# MCU.net
KiCad netlist of a schematic drawn in Altium Designer
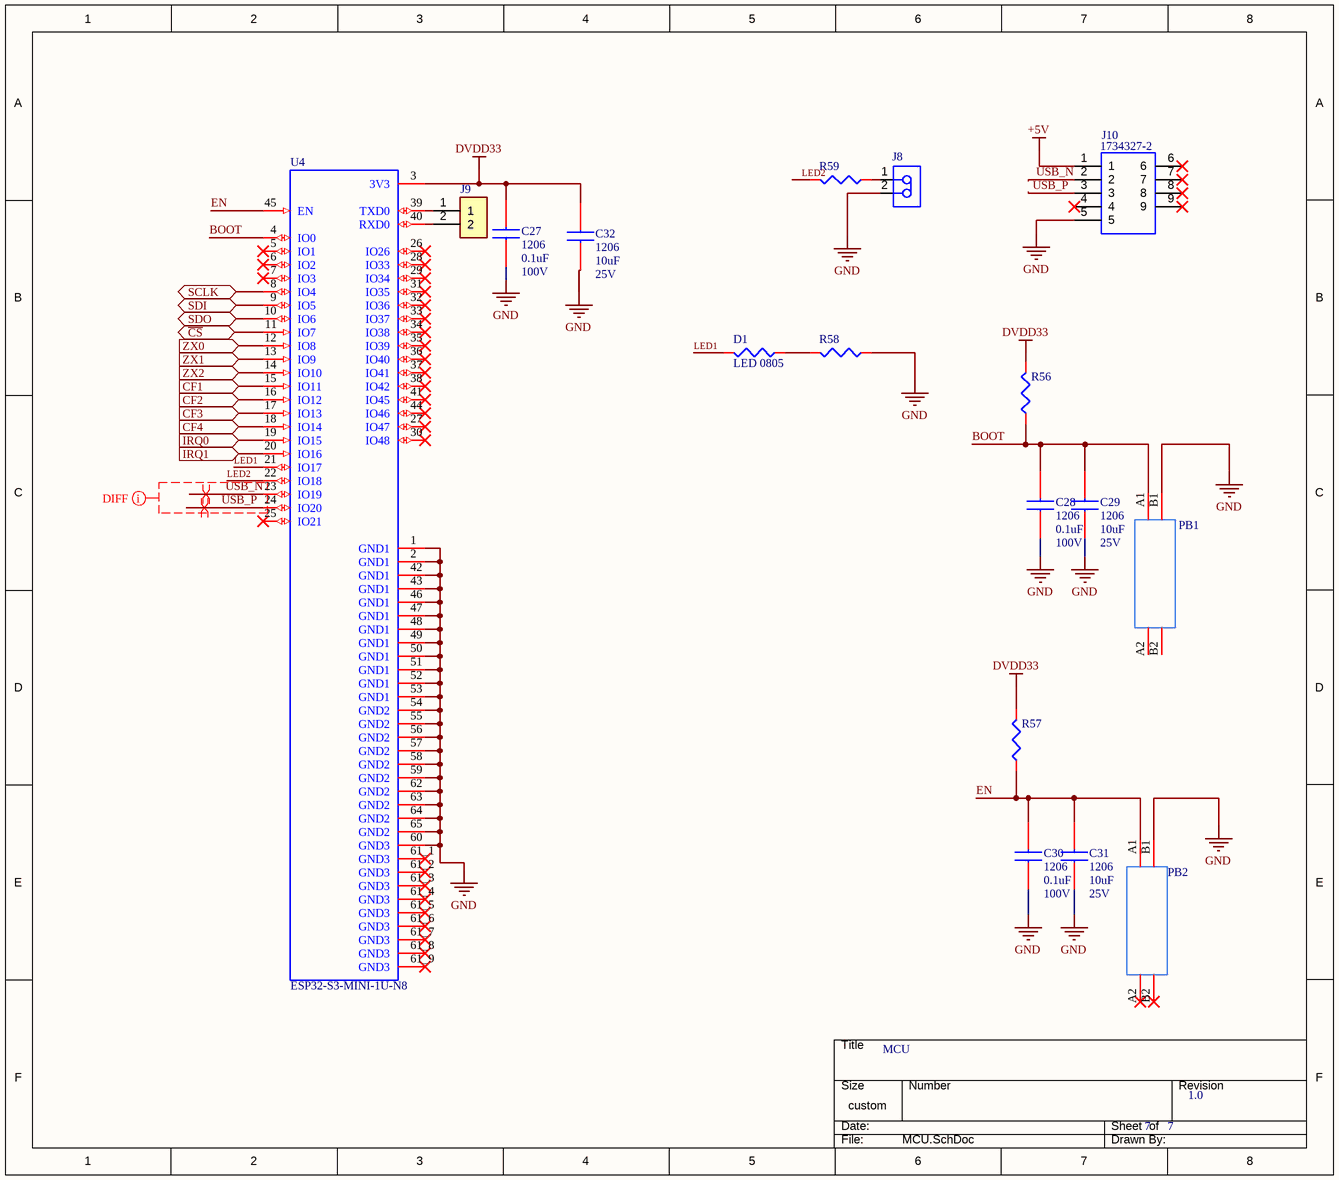
[diagram p0: MCU.SchDoc]

(export (version "E")
  (design (tool "Eeschema 10.0.6"))
  (components
    (comp (ref "C27")
      (value "C1206C104J1RACAUTO")
      (footprint "CAPC3316X180N")
      (description "Multilayer Ceramic Capacitors MLCC - SMD/SMT 100V 0.1uF X7R 1206 5% AEC-Q200")
      (fields
        (field (name "MOUSER PART NUMBER") "80-C1206X224KARAUTO")
        (field (name "MANUFACTURER_PART_NUMBER") "C1206X224KARACAUTO")
        (field (name "SIZE") "1206")
        (field (name "CAPACITANCE") "0.1uF")
        (field (name "VOLTAGE") "100V")
      )
      (libsource (lib "C1206X224KARACAUTO") (part "C1206X224KARACAUTO"))
    )
    (comp (ref "C28")
      (value "C1206C104J1RACAUTO")
      (footprint "CAPC3316X180N")
      (description "Multilayer Ceramic Capacitors MLCC - SMD/SMT 100V 0.1uF X7R 1206 5% AEC-Q200")
      (fields
        (field (name "MOUSER PART NUMBER") "80-C1206X224KARAUTO")
        (field (name "MANUFACTURER_PART_NUMBER") "C1206X224KARACAUTO")
        (field (name "SIZE") "1206")
        (field (name "CAPACITANCE") "0.1uF")
        (field (name "VOLTAGE") "100V")
      )
      (libsource (lib "C1206X224KARACAUTO") (part "C1206X224KARACAUTO"))
    )
    (comp (ref "C29")
      (value "MBAST31LAB7106KTNA01")
      (footprint "CAPC3316X180N")
      (description "Multilayer Ceramic Capacitors MLCC - SMD/SMT 25V 10uF X7R 1206 10%")
      (fields
        (field (name "MOUSER PART NUMBER") "80-C1206X224KARAUTO")
        (field (name "MANUFACTURER_PART_NUMBER") "C1206X224KARACAUTO")
        (field (name "SIZE") "1206")
        (field (name "CAPACITANCE") "10uF")
        (field (name "VOLTAGE") "25V")
      )
      (libsource (lib "C1206X224KARACAUTO") (part "C1206X224KARACAUTO"))
    )
    (comp (ref "C30")
      (value "C1206C104J1RACAUTO")
      (footprint "CAPC3316X180N")
      (description "Multilayer Ceramic Capacitors MLCC - SMD/SMT 100V 0.1uF X7R 1206 5% AEC-Q200")
      (fields
        (field (name "MOUSER PART NUMBER") "80-C1206X224KARAUTO")
        (field (name "MANUFACTURER_PART_NUMBER") "C1206X224KARACAUTO")
        (field (name "SIZE") "1206")
        (field (name "CAPACITANCE") "0.1uF")
        (field (name "VOLTAGE") "100V")
      )
      (libsource (lib "C1206X224KARACAUTO") (part "C1206X224KARACAUTO"))
    )
    (comp (ref "C31")
      (value "MBAST31LAB7106KTNA01")
      (footprint "CAPC3316X180N")
      (description "Multilayer Ceramic Capacitors MLCC - SMD/SMT 25V 10uF X7R 1206 10%")
      (fields
        (field (name "MOUSER PART NUMBER") "80-C1206X224KARAUTO")
        (field (name "MANUFACTURER_PART_NUMBER") "C1206X224KARACAUTO")
        (field (name "SIZE") "1206")
        (field (name "CAPACITANCE") "10uF")
        (field (name "VOLTAGE") "25V")
      )
      (libsource (lib "C1206X224KARACAUTO") (part "C1206X224KARACAUTO"))
    )
    (comp (ref "C32")
      (value "MBAST31LAB7106KTNA01")
      (footprint "CAPC3316X180N")
      (description "Multilayer Ceramic Capacitors MLCC - SMD/SMT 25V 10uF X7R 1206 10%")
      (fields
        (field (name "MOUSER PART NUMBER") "80-C1206X224KARAUTO")
        (field (name "MANUFACTURER_PART_NUMBER") "C1206X224KARACAUTO")
        (field (name "SIZE") "1206")
        (field (name "CAPACITANCE") "10uF")
        (field (name "VOLTAGE") "25V")
      )
      (libsource (lib "C1206X224KARACAUTO") (part "C1206X224KARACAUTO"))
    )
    (comp (ref "D1")
      (value "LED 0805")
      (footprint "RESC2013X84N")
      (description "Thin Film Resistors - SMD 0805 1000ohms 25ppm 0.5% AEC-Q200")
      (fields
        (field (name "MANUFACTURER_PART_NUMBER") "ERA-6AED102V")
        (field (name "MOUSER PART NUMBER") "667-ERA-6AED102V")
      )
      (libsource (lib "ERA-6AED102V") (part "ERA-6AED102V"))
    )
    (comp (ref "J8")
      (value "B2B-PH-K-S(LF)(SN)")
      (footprint "JST-B2B-PH-K-S_V")
      (fields (field (name "MANUFACTURER") "JST"))
      (libsource (lib "Altium Content Vault") (part "CN-2P-F-QF2"))
    )
    (comp (ref "J9")
      (value "HTSW-102-07-G-S")
      (footprint "HDRV2W64P0X254_1X2_508X248X838P")
      (description "Samtec, HTSW, 2 Way, 1 Row, Vertical Pin Header")
      (fields (field (name "MOUSER PART NUMBER") "200-HTSW10207GS"))
      (libsource (lib "HTSW-102-07-G-S") (part "HTSW-102-07-G-S"))
    )
    (comp (ref "J10")
      (value "1734327-2")
      (footprint "17343272")
      (description "Body Features: Offset 0 MM")
      (fields (field (name "MOUSER PART NUMBER") "571-1734327-2"))
      (libsource (lib "1734327-2") (part "1734327-2"))
    )
    (comp (ref "PB1")
      (value "EVP-BV2C3L000")
      (footprint "EVPBV2C3L000")
      (description "Tactile Switches 6.5mm 6.2mm SMD Op Force 1.6N")
      (fields (field (name "MOUSER PART NUMBER") "667-EVP-BV2C3L000"))
      (libsource (lib "EVP-BV2C3L000") (part "EVP-BV2C3L000"))
    )
    (comp (ref "PB2")
      (value "EVP-BV2C3L000")
      (footprint "EVPBV2C3L000")
      (description "Tactile Switches 6.5mm 6.2mm SMD Op Force 1.6N")
      (fields (field (name "MOUSER PART NUMBER") "667-EVP-BV2C3L000"))
      (libsource (lib "EVP-BV2C3L000") (part "EVP-BV2C3L000"))
    )
    (comp (ref "R56")
      (value "ERA-6AED102V")
      (footprint "RESC2013X84N")
      (description "Thin Film Resistors - SMD 0805 1000ohms 25ppm 0.5% AEC-Q200")
      (fields (field (name "MOUSER PART NUMBER") "667-ERA-6AED102V"))
      (libsource (lib "ERA-6AED102V") (part "ERA-6AED102V"))
    )
    (comp (ref "R57")
      (value "ERA-6AED102V")
      (footprint "RESC2013X84N")
      (description "Thin Film Resistors - SMD 0805 1000ohms 25ppm 0.5% AEC-Q200")
      (fields (field (name "MOUSER PART NUMBER") "667-ERA-6AED102V"))
      (libsource (lib "ERA-6AED102V") (part "ERA-6AED102V"))
    )
    (comp (ref "R58")
      (value "ERA-6AED102V")
      (footprint "RESC2013X84N")
      (description "Thin Film Resistors - SMD 0805 330ohms 25ppm 0.5% AEC-Q200")
      (fields (field (name "MOUSER PART NUMBER") "667-ERA-6AED102V"))
      (libsource (lib "ERA-6AED102V") (part "ERA-6AED102V"))
    )
    (comp (ref "R59")
      (value "ERA-6AED102V")
      (footprint "RESC2013X84N")
      (description "0805 330R")
      (fields (field (name "MOUSER PART NUMBER") "667-ERA-6AED102V"))
      (libsource (lib "ERA-6AED102V") (part "ERA-6AED102V"))
    )
    (comp (ref "U4")
      (value "ESP32-S3-MINI-1U-N8")
      (footprint "XCVR_ESP32-S3-MINI-1U-N8")
      (fields (field (name "MF") "Espressif Systems"))
      (libsource (lib "ESP32-S3-MINI-1U-N8") (part "ESP32-S3-MINI-1U-N8"))
    )
  )
  (nets
    (net (code "1") (name "+5V") (class "Default")
      (node (ref "J10") (pin "1") (pinfunction "1_1") (pintype "passive"))
    )
    (net (code "2") (name "/BOOT") (class "Default")
      (node (ref "C28") (pin "1") (pinfunction "1_1") (pintype "passive"))
      (node (ref "C29") (pin "1") (pinfunction "1_1") (pintype "passive"))
      (node (ref "PB1") (pin "A1") (pinfunction "COM_1_A1") (pintype "passive"))
      (node (ref "R56") (pin "2") (pinfunction "2_2") (pintype "passive"))
      (node (ref "U4") (pin "4") (pinfunction "IO0_4") (pintype "bidirectional"))
    )
    (net (code "3") (name "/CF1") (class "Default")
      (node (ref "U4") (pin "15") (pinfunction "IO11_15") (pintype "input"))
    )
    (net (code "4") (name "/CF2") (class "Default")
      (node (ref "U4") (pin "16") (pinfunction "IO12_16") (pintype "input"))
    )
    (net (code "5") (name "/CF3") (class "Default")
      (node (ref "U4") (pin "17") (pinfunction "IO13_17") (pintype "input"))
    )
    (net (code "6") (name "/CF4") (class "Default")
      (node (ref "U4") (pin "18") (pinfunction "IO14_18") (pintype "input"))
    )
    (net (code "7") (name "/EN") (class "Default")
      (node (ref "C30") (pin "1") (pinfunction "1_1") (pintype "passive"))
      (node (ref "C31") (pin "1") (pinfunction "1_1") (pintype "passive"))
      (node (ref "PB2") (pin "A1") (pinfunction "COM_1_A1") (pintype "passive"))
      (node (ref "R57") (pin "2") (pinfunction "2_2") (pintype "passive"))
      (node (ref "U4") (pin "45") (pinfunction "EN_45") (pintype "input"))
    )
    (net (code "8") (name "/IRQ0") (class "Default")
      (node (ref "U4") (pin "19") (pinfunction "IO15_19") (pintype "input"))
    )
    (net (code "9") (name "/IRQ1") (class "Default")
      (node (ref "U4") (pin "20") (pinfunction "IO16_20") (pintype "input"))
    )
    (net (code "10") (name "/LED1") (class "Default")
      (node (ref "D1") (pin "1") (pinfunction "1_1") (pintype "passive"))
      (node (ref "U4") (pin "21") (pinfunction "IO17_21") (pintype "bidirectional"))
    )
    (net (code "11") (name "/LED2") (class "Default")
      (node (ref "R59") (pin "2") (pinfunction "2_2") (pintype "passive"))
      (node (ref "U4") (pin "22") (pinfunction "IO18_22") (pintype "bidirectional"))
    )
    (net (code "12") (name "/SCLK") (class "Default")
      (node (ref "U4") (pin "8") (pinfunction "IO4_8") (pintype "bidirectional"))
    )
    (net (code "13") (name "/SDI") (class "Default")
      (node (ref "U4") (pin "9") (pinfunction "IO5_9") (pintype "bidirectional"))
    )
    (net (code "14") (name "/SDO") (class "Default")
      (node (ref "U4") (pin "10") (pinfunction "IO6_10") (pintype "bidirectional"))
    )
    (net (code "15") (name "/USB_N") (class "Default")
      (node (ref "J10") (pin "2") (pinfunction "2_2") (pintype "passive"))
      (node (ref "U4") (pin "23") (pinfunction "IO19_23") (pintype "bidirectional"))
    )
    (net (code "16") (name "/USB_P") (class "Default")
      (node (ref "J10") (pin "3") (pinfunction "3_3") (pintype "passive"))
      (node (ref "U4") (pin "24") (pinfunction "IO20_24") (pintype "bidirectional"))
    )
    (net (code "17") (name "/ZX0") (class "Default")
      (node (ref "U4") (pin "12") (pinfunction "IO8_12") (pintype "input"))
    )
    (net (code "18") (name "/ZX1") (class "Default")
      (node (ref "U4") (pin "13") (pinfunction "IO9_13") (pintype "input"))
    )
    (net (code "19") (name "/ZX2") (class "Default")
      (node (ref "U4") (pin "14") (pinfunction "IO10_14") (pintype "input"))
    )
    (net (code "20") (name "/~{CS}") (class "Default")
      (node (ref "U4") (pin "11") (pinfunction "IO7_11") (pintype "input"))
    )
    (net (code "21") (name "DVDD33") (class "Default")
      (node (ref "C27") (pin "1") (pinfunction "1_1") (pintype "passive"))
      (node (ref "C32") (pin "1") (pinfunction "1_1") (pintype "passive"))
      (node (ref "R56") (pin "1") (pinfunction "1_1") (pintype "passive"))
      (node (ref "R57") (pin "1") (pinfunction "1_1") (pintype "passive"))
      (node (ref "U4") (pin "3") (pinfunction "3V3_3") (pintype "power_in"))
    )
    (net (code "22") (name "GND") (class "Default")
      (node (ref "C27") (pin "2") (pinfunction "2_2") (pintype "passive"))
      (node (ref "C28") (pin "2") (pinfunction "2_2") (pintype "passive"))
      (node (ref "C29") (pin "2") (pinfunction "2_2") (pintype "passive"))
      (node (ref "C30") (pin "2") (pinfunction "2_2") (pintype "passive"))
      (node (ref "C31") (pin "2") (pinfunction "2_2") (pintype "passive"))
      (node (ref "C32") (pin "2") (pinfunction "2_2") (pintype "passive"))
      (node (ref "J10") (pin "5") (pinfunction "5_5") (pintype "passive"))
      (node (ref "J8") (pin "2") (pinfunction "2_2") (pintype "passive"))
      (node (ref "PB1") (pin "B1") (pinfunction "NO_1_B1") (pintype "passive"))
      (node (ref "PB2") (pin "B1") (pinfunction "NO_1_B1") (pintype "passive"))
      (node (ref "R58") (pin "2") (pinfunction "2_2") (pintype "passive"))
      (node (ref "U4") (pin "1") (pinfunction "GND1_1") (pintype "power_in"))
      (node (ref "U4") (pin "2") (pinfunction "GND1_2") (pintype "power_in"))
      (node (ref "U4") (pin "42") (pinfunction "GND1_42") (pintype "power_in"))
      (node (ref "U4") (pin "43") (pinfunction "GND1_43") (pintype "power_in"))
      (node (ref "U4") (pin "46") (pinfunction "GND1_46") (pintype "power_in"))
      (node (ref "U4") (pin "47") (pinfunction "GND1_47") (pintype "power_in"))
      (node (ref "U4") (pin "48") (pinfunction "GND1_48") (pintype "power_in"))
      (node (ref "U4") (pin "49") (pinfunction "GND1_49") (pintype "power_in"))
      (node (ref "U4") (pin "50") (pinfunction "GND1_50") (pintype "power_in"))
      (node (ref "U4") (pin "51") (pinfunction "GND1_51") (pintype "power_in"))
      (node (ref "U4") (pin "52") (pinfunction "GND1_52") (pintype "power_in"))
      (node (ref "U4") (pin "53") (pinfunction "GND1_53") (pintype "power_in"))
      (node (ref "U4") (pin "54") (pinfunction "GND2_54") (pintype "power_in"))
      (node (ref "U4") (pin "55") (pinfunction "GND2_55") (pintype "power_in"))
      (node (ref "U4") (pin "56") (pinfunction "GND2_56") (pintype "power_in"))
      (node (ref "U4") (pin "57") (pinfunction "GND2_57") (pintype "power_in"))
      (node (ref "U4") (pin "58") (pinfunction "GND2_58") (pintype "power_in"))
      (node (ref "U4") (pin "59") (pinfunction "GND2_59") (pintype "power_in"))
      (node (ref "U4") (pin "60") (pinfunction "GND3_60") (pintype "power_in"))
      (node (ref "U4") (pin "62") (pinfunction "GND2_62") (pintype "power_in"))
      (node (ref "U4") (pin "63") (pinfunction "GND2_63") (pintype "power_in"))
      (node (ref "U4") (pin "64") (pinfunction "GND2_64") (pintype "power_in"))
      (node (ref "U4") (pin "65") (pinfunction "GND2_65") (pintype "power_in"))
    )
    (net (code "23") (name "Net-(D1-Pad2)") (class "Default")
      (node (ref "D1") (pin "2") (pinfunction "2_2") (pintype "passive"))
      (node (ref "R58") (pin "1") (pinfunction "1_1") (pintype "passive"))
    )
    (net (code "24") (name "Net-(J8-Pad1)") (class "Default")
      (node (ref "J8") (pin "1") (pinfunction "1_1") (pintype "passive"))
      (node (ref "R59") (pin "1") (pinfunction "1_1") (pintype "passive"))
    )
    (net (code "25") (name "Net-(U4-RXD0)") (class "Default")
      (node (ref "J9") (pin "2") (pinfunction "2_2") (pintype "passive"))
      (node (ref "U4") (pin "40") (pinfunction "RXD0_40") (pintype "bidirectional"))
    )
    (net (code "26") (name "Net-(U4-TXD0)") (class "Default")
      (node (ref "J9") (pin "1") (pinfunction "1_1") (pintype "passive"))
      (node (ref "U4") (pin "39") (pinfunction "TXD0_39") (pintype "bidirectional"))
    )
    (net (code "27") (name "unconnected-(J10-Pad4)") (class "Default")
      (node (ref "J10") (pin "4") (pinfunction "4_4") (pintype "passive+no_connect"))
    )
    (net (code "28") (name "unconnected-(J10-Pad6)") (class "Default")
      (node (ref "J10") (pin "6") (pinfunction "6_6") (pintype "passive+no_connect"))
    )
    (net (code "29") (name "unconnected-(J10-Pad7)") (class "Default")
      (node (ref "J10") (pin "7") (pinfunction "7_7") (pintype "passive+no_connect"))
    )
    (net (code "30") (name "unconnected-(J10-Pad8)") (class "Default")
      (node (ref "J10") (pin "8") (pinfunction "8_8") (pintype "passive+no_connect"))
    )
    (net (code "31") (name "unconnected-(J10-Pad9)") (class "Default")
      (node (ref "J10") (pin "9") (pinfunction "9_9") (pintype "passive+no_connect"))
    )
    (net (code "32") (name "unconnected-(PB1-COM_2-PadA2)") (class "Default")
      (node (ref "PB1") (pin "A2") (pinfunction "COM_2_A2") (pintype "passive"))
    )
    (net (code "33") (name "unconnected-(PB1-NO_2-PadB2)") (class "Default")
      (node (ref "PB1") (pin "B2") (pinfunction "NO_2_B2") (pintype "passive"))
    )
    (net (code "34") (name "unconnected-(PB2-COM_2-PadA2)") (class "Default")
      (node (ref "PB2") (pin "A2") (pinfunction "COM_2_A2") (pintype "passive+no_connect"))
    )
    (net (code "35") (name "unconnected-(PB2-NO_2-PadB2)") (class "Default")
      (node (ref "PB2") (pin "B2") (pinfunction "NO_2_B2") (pintype "passive+no_connect"))
    )
    (net (code "36") (name "unconnected-(U4-GND3-Pad61_1)") (class "Default")
      (node (ref "U4") (pin "61_1") (pinfunction "GND3_61_1") (pintype "power_in+no_connect"))
    )
    (net (code "37") (name "unconnected-(U4-GND3-Pad61_2)") (class "Default")
      (node (ref "U4") (pin "61_2") (pinfunction "GND3_61_2") (pintype "power_in+no_connect"))
    )
    (net (code "38") (name "unconnected-(U4-GND3-Pad61_3)") (class "Default")
      (node (ref "U4") (pin "61_3") (pinfunction "GND3_61_3") (pintype "power_in+no_connect"))
    )
    (net (code "39") (name "unconnected-(U4-GND3-Pad61_4)") (class "Default")
      (node (ref "U4") (pin "61_4") (pinfunction "GND3_61_4") (pintype "power_in+no_connect"))
    )
    (net (code "40") (name "unconnected-(U4-GND3-Pad61_5)") (class "Default")
      (node (ref "U4") (pin "61_5") (pinfunction "GND3_61_5") (pintype "power_in+no_connect"))
    )
    (net (code "41") (name "unconnected-(U4-GND3-Pad61_6)") (class "Default")
      (node (ref "U4") (pin "61_6") (pinfunction "GND3_61_6") (pintype "power_in+no_connect"))
    )
    (net (code "42") (name "unconnected-(U4-GND3-Pad61_7)") (class "Default")
      (node (ref "U4") (pin "61_7") (pinfunction "GND3_61_7") (pintype "power_in+no_connect"))
    )
    (net (code "43") (name "unconnected-(U4-GND3-Pad61_8)") (class "Default")
      (node (ref "U4") (pin "61_8") (pinfunction "GND3_61_8") (pintype "power_in+no_connect"))
    )
    (net (code "44") (name "unconnected-(U4-GND3-Pad61_9)") (class "Default")
      (node (ref "U4") (pin "61_9") (pinfunction "GND3_61_9") (pintype "power_in+no_connect"))
    )
    (net (code "45") (name "unconnected-(U4-IO1-Pad5)") (class "Default")
      (node (ref "U4") (pin "5") (pinfunction "IO1_5") (pintype "bidirectional+no_connect"))
    )
    (net (code "46") (name "unconnected-(U4-IO2-Pad6)") (class "Default")
      (node (ref "U4") (pin "6") (pinfunction "IO2_6") (pintype "bidirectional+no_connect"))
    )
    (net (code "47") (name "unconnected-(U4-IO3-Pad7)") (class "Default")
      (node (ref "U4") (pin "7") (pinfunction "IO3_7") (pintype "bidirectional+no_connect"))
    )
    (net (code "48") (name "unconnected-(U4-IO21-Pad25)") (class "Default")
      (node (ref "U4") (pin "25") (pinfunction "IO21_25") (pintype "bidirectional+no_connect"))
    )
    (net (code "49") (name "unconnected-(U4-IO26-Pad26)") (class "Default")
      (node (ref "U4") (pin "26") (pinfunction "IO26_26") (pintype "bidirectional+no_connect"))
    )
    (net (code "50") (name "unconnected-(U4-IO33-Pad28)") (class "Default")
      (node (ref "U4") (pin "28") (pinfunction "IO33_28") (pintype "bidirectional+no_connect"))
    )
    (net (code "51") (name "unconnected-(U4-IO34-Pad29)") (class "Default")
      (node (ref "U4") (pin "29") (pinfunction "IO34_29") (pintype "bidirectional+no_connect"))
    )
    (net (code "52") (name "unconnected-(U4-IO35-Pad31)") (class "Default")
      (node (ref "U4") (pin "31") (pinfunction "IO35_31") (pintype "bidirectional+no_connect"))
    )
    (net (code "53") (name "unconnected-(U4-IO36-Pad32)") (class "Default")
      (node (ref "U4") (pin "32") (pinfunction "IO36_32") (pintype "bidirectional+no_connect"))
    )
    (net (code "54") (name "unconnected-(U4-IO37-Pad33)") (class "Default")
      (node (ref "U4") (pin "33") (pinfunction "IO37_33") (pintype "bidirectional+no_connect"))
    )
    (net (code "55") (name "unconnected-(U4-IO38-Pad34)") (class "Default")
      (node (ref "U4") (pin "34") (pinfunction "IO38_34") (pintype "bidirectional+no_connect"))
    )
    (net (code "56") (name "unconnected-(U4-IO39-Pad35)") (class "Default")
      (node (ref "U4") (pin "35") (pinfunction "IO39_35") (pintype "bidirectional+no_connect"))
    )
    (net (code "57") (name "unconnected-(U4-IO40-Pad36)") (class "Default")
      (node (ref "U4") (pin "36") (pinfunction "IO40_36") (pintype "bidirectional+no_connect"))
    )
    (net (code "58") (name "unconnected-(U4-IO41-Pad37)") (class "Default")
      (node (ref "U4") (pin "37") (pinfunction "IO41_37") (pintype "bidirectional+no_connect"))
    )
    (net (code "59") (name "unconnected-(U4-IO42-Pad38)") (class "Default")
      (node (ref "U4") (pin "38") (pinfunction "IO42_38") (pintype "bidirectional+no_connect"))
    )
    (net (code "60") (name "unconnected-(U4-IO45-Pad41)") (class "Default")
      (node (ref "U4") (pin "41") (pinfunction "IO45_41") (pintype "bidirectional+no_connect"))
    )
    (net (code "61") (name "unconnected-(U4-IO46-Pad44)") (class "Default")
      (node (ref "U4") (pin "44") (pinfunction "IO46_44") (pintype "bidirectional+no_connect"))
    )
    (net (code "62") (name "unconnected-(U4-IO47-Pad27)") (class "Default")
      (node (ref "U4") (pin "27") (pinfunction "IO47_27") (pintype "bidirectional+no_connect"))
    )
    (net (code "63") (name "unconnected-(U4-IO48-Pad30)") (class "Default")
      (node (ref "U4") (pin "30") (pinfunction "IO48_30") (pintype "bidirectional+no_connect"))
    )
  )
)
